# 04_IF_AMP_Block.net
KiCad netlist of a schematic drawn in Altium Designer
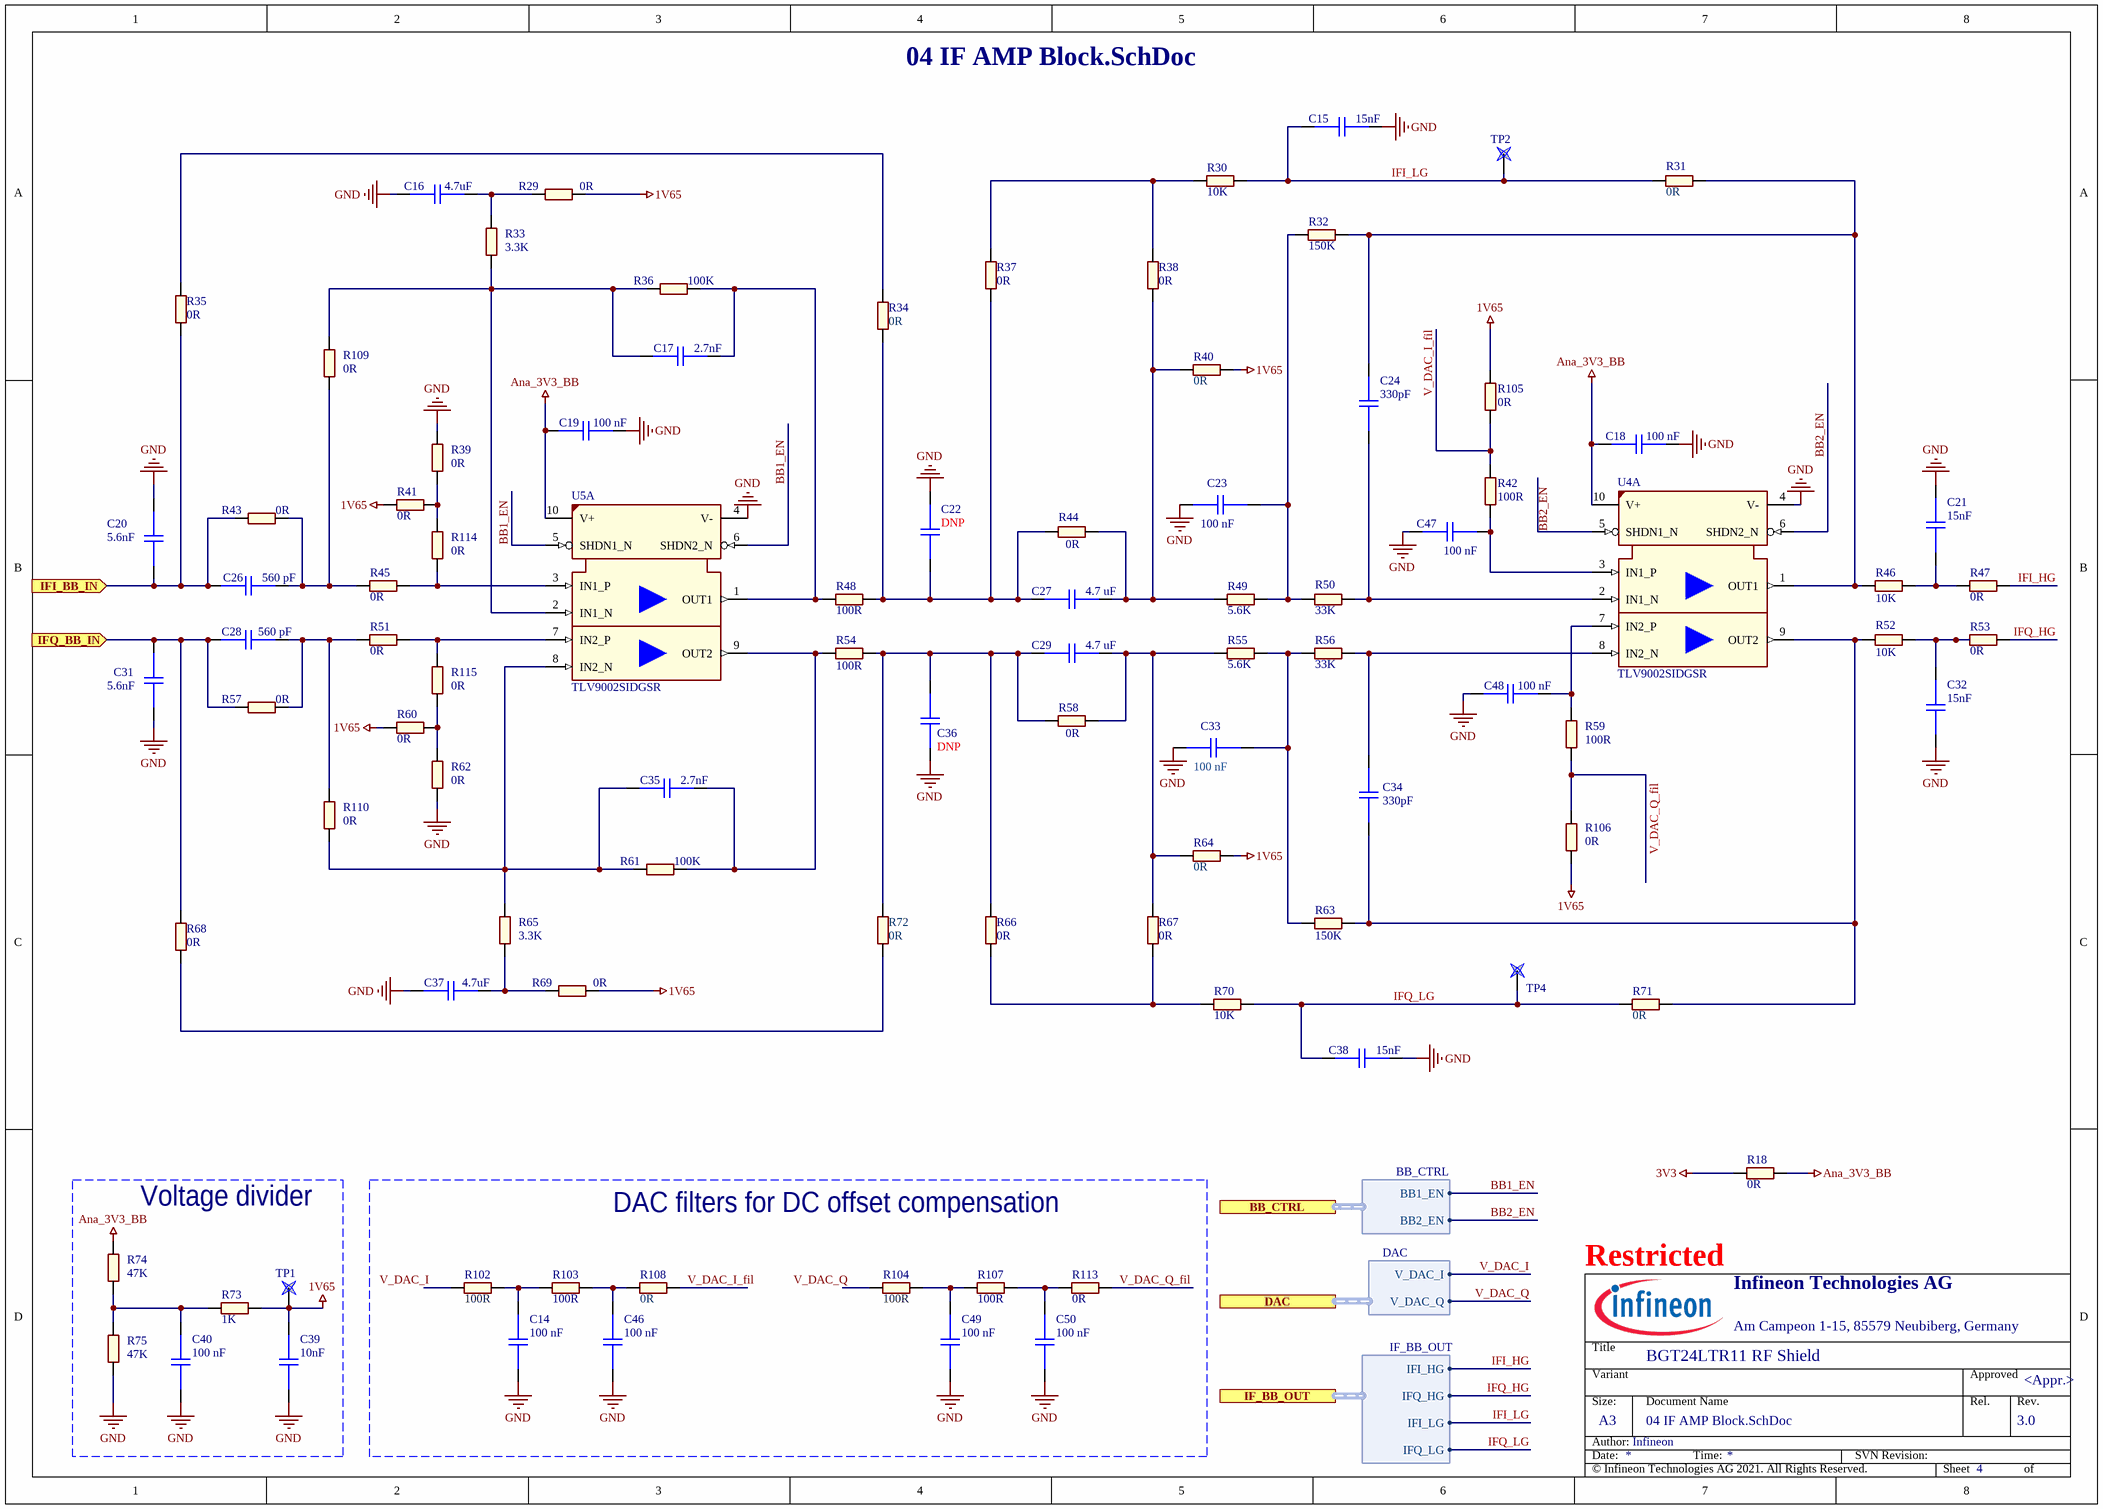
[diagram p0: 04 IF AMP Block.SchDoc]

(export (version "E")
  (design (tool "Eeschema 10.0.6"))
  (components
    (comp (ref "C14")
      (value "100 nF")
      (footprint "CAPC1005X55N-0_2")
      (description "General Purpose Surface Mount Ceramic Capacitor")
      (fields (field (name "PARTNUMBER") "CAP01010597") (field (name "VOLTAGE") "16Vdc"))
      (libsource (lib "DB_External_Capacitor") (part "c_std_a"))
    )
    (comp (ref "C15")
      (value "15nF")
      (footprint "CAPC1005X55N-0_2")
      (description "General Purpose Surface Mount Ceramic Capacitor")
      (fields (field (name "PARTNUMBER") "CAP01010597") (field (name "VOLTAGE") "25Vdc"))
      (libsource (lib "DB_External_Capacitor") (part "c_std_a"))
    )
    (comp (ref "C16")
      (value "4.7uF")
      (footprint "CAPC1005X55N-0_2")
      (description "General Purpose Surface Mount Ceramic Capacitor")
      (fields (field (name "PARTNUMBER") "CAP01010597") (field (name "VOLTAGE") "50Vdc"))
      (libsource (lib "DB_External_Capacitor") (part "c_std_a"))
    )
    (comp (ref "C17")
      (value "2.7nF")
      (footprint "CAPC1005X55N-0_2")
      (description "General Purpose Surface Mount Ceramic Capacitor")
      (fields (field (name "PARTNUMBER") "CAP01010597") (field (name "VOLTAGE") "50Vdc"))
      (libsource (lib "DB_External_Capacitor") (part "c_std_a"))
    )
    (comp (ref "C18")
      (value "100 nF")
      (footprint "CAPC1005X55N-0_2")
      (description "General Purpose Surface Mount Ceramic Capacitor")
      (fields (field (name "PARTNUMBER") "CAP01010597") (field (name "VOLTAGE") "16Vdc"))
      (libsource (lib "DB_External_Capacitor") (part "c_std_a"))
    )
    (comp (ref "C19")
      (value "100 nF")
      (footprint "CAPC1005X55N-0_2")
      (description "General Purpose Surface Mount Ceramic Capacitor")
      (fields (field (name "PARTNUMBER") "CAP01010597") (field (name "VOLTAGE") "16Vdc"))
      (libsource (lib "DB_External_Capacitor") (part "c_std_a"))
    )
    (comp (ref "C20")
      (value "5.6nF")
      (footprint "CAPC1005X55N-0_2")
      (description "General Purpose Surface Mount Ceramic Capacitor")
      (fields (field (name "PARTNUMBER") "CAP01010597") (field (name "VOLTAGE") "50Vdc"))
      (libsource (lib "DB_External_Capacitor") (part "c_std_a"))
    )
    (comp (ref "C21")
      (value "15nF")
      (footprint "CAPC1005X55N-0_2")
      (description "General Purpose Surface Mount Ceramic Capacitor")
      (fields (field (name "PARTNUMBER") "CAP01010597") (field (name "VOLTAGE") "25Vdc"))
      (libsource (lib "DB_External_Capacitor") (part "c_std_a"))
    )
    (comp (ref "C22")
      (value "DNP")
      (footprint "CAPC1005X55N-0_2")
      (description "General Purpose Surface Mount Ceramic Capacitor")
      (fields (field (name "PARTNUMBER") "CAP01010597") (field (name "VOLTAGE") "50Vdc"))
      (libsource (lib "DB_External_Capacitor") (part "c_std_a"))
    )
    (comp (ref "C23")
      (value "100 nF")
      (footprint "CAPC1005X55N-0_2")
      (description "General Purpose Surface Mount Ceramic Capacitor")
      (fields (field (name "PARTNUMBER") "CAP01010597") (field (name "VOLTAGE") "16Vdc"))
      (libsource (lib "DB_External_Capacitor") (part "c_std_a"))
    )
    (comp (ref "C24")
      (value "330pF")
      (footprint "CAPC1005X55N-0_2")
      (description "General Purpose Surface Mount Ceramic Capacitor")
      (fields (field (name "PARTNUMBER") "CAP01010597") (field (name "VOLTAGE") "50Vdc"))
      (libsource (lib "DB_External_Capacitor") (part "c_std_a"))
    )
    (comp (ref "C26")
      (value "560 pF")
      (footprint "CAPC1005X55N-0_2")
      (description "General Purpose Surface Mount Ceramic Capacitor")
      (fields (field (name "PARTNUMBER") "CAP01010597") (field (name "VOLTAGE") "50Vdc"))
      (libsource (lib "DB_External_Capacitor") (part "c_std_a"))
    )
    (comp (ref "C27")
      (value "4.7 uF")
      (footprint "CAPC1005X55N-0_2")
      (description "General Purpose Surface Mount Ceramic Capacitor")
      (fields (field (name "PARTNUMBER") "CAP01010597") (field (name "VOLTAGE") "50Vdc"))
      (libsource (lib "DB_External_Capacitor") (part "c_std_a"))
    )
    (comp (ref "C28")
      (value "560 pF")
      (footprint "CAPC1005X55N-0_2")
      (description "General Purpose Surface Mount Ceramic Capacitor")
      (fields (field (name "PARTNUMBER") "CAP01010597") (field (name "VOLTAGE") "50Vdc"))
      (libsource (lib "DB_External_Capacitor") (part "c_std_a"))
    )
    (comp (ref "C29")
      (value "4.7 uF")
      (footprint "CAPC1005X55N-0_2")
      (description "General Purpose Surface Mount Ceramic Capacitor")
      (fields (field (name "PARTNUMBER") "CAP01010597") (field (name "VOLTAGE") "50Vdc"))
      (libsource (lib "DB_External_Capacitor") (part "c_std_a"))
    )
    (comp (ref "C31")
      (value "5.6nF")
      (footprint "CAPC1005X55N-0_2")
      (description "General Purpose Surface Mount Ceramic Capacitor")
      (fields (field (name "PARTNUMBER") "CAP01010597") (field (name "VOLTAGE") "50Vdc"))
      (libsource (lib "DB_External_Capacitor") (part "c_std_a"))
    )
    (comp (ref "C32")
      (value "15nF")
      (footprint "CAPC1005X55N-0_2")
      (description "General Purpose Surface Mount Ceramic Capacitor")
      (fields (field (name "PARTNUMBER") "CAP01010597") (field (name "VOLTAGE") "25Vdc"))
      (libsource (lib "DB_External_Capacitor") (part "c_std_a"))
    )
    (comp (ref "C33")
      (value "100 nF")
      (footprint "CAPC1005X55N-0_2")
      (description "General Purpose Surface Mount Ceramic Capacitor")
      (fields (field (name "PARTNUMBER") "CAP01010597") (field (name "VOLTAGE") "16Vdc"))
      (libsource (lib "DB_External_Capacitor") (part "c_std_a"))
    )
    (comp (ref "C34")
      (value "330pF")
      (footprint "CAPC1005X55N-0_2")
      (description "General Purpose Surface Mount Ceramic Capacitor")
      (fields (field (name "PARTNUMBER") "CAP01010597") (field (name "VOLTAGE") "50Vdc"))
      (libsource (lib "DB_External_Capacitor") (part "c_std_a"))
    )
    (comp (ref "C35")
      (value "2.7nF")
      (footprint "CAPC1005X55N-0_2")
      (description "General Purpose Surface Mount Ceramic Capacitor")
      (fields (field (name "PARTNUMBER") "CAP01010597") (field (name "VOLTAGE") "50Vdc"))
      (libsource (lib "DB_External_Capacitor") (part "c_std_a"))
    )
    (comp (ref "C36")
      (value "DNP")
      (footprint "CAPC1005X55N-0_2")
      (description "General Purpose Surface Mount Ceramic Capacitor")
      (fields (field (name "PARTNUMBER") "CAP01010597") (field (name "VOLTAGE") "50Vdc"))
      (libsource (lib "DB_External_Capacitor") (part "c_std_a"))
    )
    (comp (ref "C37")
      (value "4.7uF")
      (footprint "CAPC1005X55N-0_2")
      (description "General Purpose Surface Mount Ceramic Capacitor")
      (fields (field (name "PARTNUMBER") "CAP01010597") (field (name "VOLTAGE") "50Vdc"))
      (libsource (lib "DB_External_Capacitor") (part "c_std_a"))
    )
    (comp (ref "C38")
      (value "15nF")
      (footprint "CAPC1005X55N-0_2")
      (description "General Purpose Surface Mount Ceramic Capacitor")
      (fields (field (name "PARTNUMBER") "CAP01010597") (field (name "VOLTAGE") "25Vdc"))
      (libsource (lib "DB_External_Capacitor") (part "c_std_a"))
    )
    (comp (ref "C39")
      (value "10nF")
      (footprint "CAPC1005X55N-0_2")
      (description "General Purpose Surface Mount Ceramic Capacitor")
      (fields (field (name "PARTNUMBER") "CAP01010597") (field (name "VOLTAGE") "16Vdc"))
      (libsource (lib "DB_External_Capacitor") (part "c_std_a"))
    )
    (comp (ref "C40")
      (value "100 nF")
      (footprint "CAPC1005X55N-0_2")
      (description "General Purpose Surface Mount Ceramic Capacitor")
      (fields (field (name "PARTNUMBER") "CAP01010597") (field (name "VOLTAGE") "16Vdc"))
      (libsource (lib "DB_External_Capacitor") (part "c_std_a"))
    )
    (comp (ref "C46")
      (value "100 nF")
      (footprint "CAPC1005X55N-0_2")
      (description "General Purpose Surface Mount Ceramic Capacitor")
      (fields (field (name "PARTNUMBER") "CAP01010597") (field (name "VOLTAGE") "16Vdc"))
      (libsource (lib "DB_External_Capacitor") (part "c_std_a"))
    )
    (comp (ref "C47")
      (value "100 nF")
      (footprint "CAPC1005X55N-0_2")
      (description "General Purpose Surface Mount Ceramic Capacitor")
      (fields (field (name "PARTNUMBER") "CAP01010597") (field (name "VOLTAGE") "16Vdc"))
      (libsource (lib "DB_External_Capacitor") (part "c_std_a"))
    )
    (comp (ref "C48")
      (value "100 nF")
      (footprint "CAPC1005X55N-0_2")
      (description "General Purpose Surface Mount Ceramic Capacitor")
      (fields (field (name "PARTNUMBER") "CAP01010597") (field (name "VOLTAGE") "16Vdc"))
      (libsource (lib "DB_External_Capacitor") (part "c_std_a"))
    )
    (comp (ref "C49")
      (value "100 nF")
      (footprint "CAPC1005X55N-0_2")
      (description "General Purpose Surface Mount Ceramic Capacitor")
      (fields (field (name "PARTNUMBER") "CAP01010597") (field (name "VOLTAGE") "16Vdc"))
      (libsource (lib "DB_External_Capacitor") (part "c_std_a"))
    )
    (comp (ref "C50")
      (value "100 nF")
      (footprint "CAPC1005X55N-0_2")
      (description "General Purpose Surface Mount Ceramic Capacitor")
      (fields (field (name "PARTNUMBER") "CAP01010597") (field (name "VOLTAGE") "16Vdc"))
      (libsource (lib "DB_External_Capacitor") (part "c_std_a"))
    )
    (comp (ref "R18")
      (value "0R")
      (footprint "RESC1005X40N_2")
      (description "0R/50V/20mOhm")
      (fields (field (name "PARTNUMBER") "RES01800000") (field (name "POWER") "1.5A"))
      (libsource (lib "DB_External_Resistor") (part "r_std_a"))
    )
    (comp (ref "R29")
      (value "0R")
      (footprint "RESC1005X40N_2")
      (description "0R/50V/20mOhm")
      (fields (field (name "PARTNUMBER") "RES01800000") (field (name "POWER") "1.5A"))
      (libsource (lib "") (part "r_std_a_3"))
    )
    (comp (ref "R30")
      (value "10K")
      (footprint "RESC1005X40N_2")
      (description "10K/50V/20mOhm")
      (fields (field (name "PARTNUMBER") "RES01800000") (field (name "POWER") "1.5A"))
      (libsource (lib "") (part "r_std_a_2"))
    )
    (comp (ref "R31")
      (value "0R")
      (footprint "RESC1005X40N_2")
      (description "0R/50V/20mOhm")
      (fields (field (name "PARTNUMBER") "RES01800000") (field (name "POWER") "1.5A"))
      (libsource (lib "") (part "r_std_a_3"))
    )
    (comp (ref "R32")
      (value "150K")
      (footprint "RESC1005X40N_2")
      (description "150K/50V/20mOhm")
      (fields (field (name "PARTNUMBER") "RES01800000") (field (name "POWER") "1.5A"))
      (libsource (lib "DB_External_Resistor") (part "r_std_a"))
    )
    (comp (ref "R33")
      (value "3.3K")
      (footprint "RESC1005X40N_2")
      (description "3.3K/50V/20mOhm")
      (fields (field (name "PARTNUMBER") "RES01800000") (field (name "POWER") "1.5A"))
      (libsource (lib "") (part "r_std_a_2"))
    )
    (comp (ref "R34")
      (value "0R")
      (footprint "RESC1005X40N_2")
      (description "0R/50V/20mOhm")
      (fields (field (name "PARTNUMBER") "RES01800000") (field (name "POWER") "1.5A"))
      (libsource (lib "DB_External_Resistor") (part "r_std_a"))
    )
    (comp (ref "R35")
      (value "0R")
      (footprint "RESC1005X40N_2")
      (description "0R/50V/20mOhm")
      (fields (field (name "PARTNUMBER") "RES01800000") (field (name "POWER") "1.5A"))
      (libsource (lib "DB_External_Resistor") (part "r_std_a"))
    )
    (comp (ref "R36")
      (value "100K")
      (footprint "RESC1005X40N_2")
      (description "100K/50V/0402")
      (fields (field (name "PARTNUMBER") "RES01800000") (field (name "POWER") "1.5A"))
      (libsource (lib "") (part "r_std_a_3"))
    )
    (comp (ref "R37")
      (value "0R")
      (footprint "RESC1005X40N_2")
      (description "0R/50V/20mOhm")
      (fields (field (name "PARTNUMBER") "RES01800000") (field (name "POWER") "1.5A"))
      (libsource (lib "") (part "r_std_a_1"))
    )
    (comp (ref "R38")
      (value "0R")
      (footprint "RESC1005X40N_2")
      (description "0R/50V/20mOhm")
      (fields (field (name "PARTNUMBER") "RES01800000") (field (name "POWER") "1.5A"))
      (libsource (lib "") (part "r_std_a_1"))
    )
    (comp (ref "R39")
      (value "0R")
      (footprint "RESC1005X40N_2")
      (description "0R/50V/20mOhm")
      (fields (field (name "PARTNUMBER") "RES01800000") (field (name "POWER") "1.5A"))
      (libsource (lib "") (part "r_std_a_1"))
    )
    (comp (ref "R40")
      (value "0R")
      (footprint "RESC1005X40N_2")
      (description "0R/50V/20mOhm")
      (fields (field (name "PARTNUMBER") "RES01800000") (field (name "POWER") "1.5A"))
      (libsource (lib "") (part "r_std_a_3"))
    )
    (comp (ref "R41")
      (value "0R")
      (footprint "RESC1005X40N_2")
      (description "0R/50V/20mOhm")
      (fields (field (name "PARTNUMBER") "RES01800000") (field (name "POWER") "1.5A"))
      (libsource (lib "") (part "r_std_a_2"))
    )
    (comp (ref "R42")
      (value "100R")
      (footprint "RESC1005X40N_2")
      (description "100R/50V/0402")
      (fields (field (name "PARTNUMBER") "RES01800000") (field (name "POWER") "1.5A"))
      (libsource (lib "") (part "r_std_a_2"))
    )
    (comp (ref "R43")
      (value "0R")
      (footprint "RESC1005X40N_2")
      (description "0R/50V/20mOhm")
      (fields (field (name "PARTNUMBER") "RES01800000") (field (name "POWER") "1.5A"))
      (libsource (lib "") (part "r_std_a_3"))
    )
    (comp (ref "R44")
      (value "0R")
      (footprint "RESC1005X40N_2")
      (description "0R/50V/20mOhm")
      (fields (field (name "PARTNUMBER") "RES01800000") (field (name "POWER") "1.5A"))
      (libsource (lib "") (part "r_std_a_3"))
    )
    (comp (ref "R45")
      (value "0R")
      (footprint "RESC1005X40N_2")
      (description "0R/50V/20mOhm")
      (fields (field (name "PARTNUMBER") "RES01800000") (field (name "POWER") "1.5A"))
      (libsource (lib "") (part "r_std_a_3"))
    )
    (comp (ref "R46")
      (value "10K")
      (footprint "RESC1005X40N_2")
      (description "10K/50V/20mOhm")
      (fields (field (name "PARTNUMBER") "RES01800000") (field (name "POWER") "1.5A"))
      (libsource (lib "") (part "r_std_a_3"))
    )
    (comp (ref "R47")
      (value "0R")
      (footprint "RESC1005X40N_2")
      (description "0R/50V/20mOhm")
      (fields (field (name "PARTNUMBER") "RES01800000") (field (name "POWER") "1.5A"))
      (libsource (lib "") (part "r_std_a_3"))
    )
    (comp (ref "R48")
      (value "100R")
      (footprint "RESC1005X40N_2")
      (description "100R/50V/0402")
      (fields (field (name "PARTNUMBER") "RES01800000") (field (name "POWER") "1.5A"))
      (libsource (lib "") (part "r_std_a_3"))
    )
    (comp (ref "R49")
      (value "5.6K")
      (footprint "RESC1005X40N_2")
      (description "5.6K/50V/20mOhm")
      (fields (field (name "PARTNUMBER") "RES01800000") (field (name "POWER") "1.5A"))
      (libsource (lib "") (part "r_std_a_3"))
    )
    (comp (ref "R50")
      (value "33K")
      (footprint "RESC1005X40N_2")
      (description "5.6K/50V/20mOhm")
      (fields (field (name "PARTNUMBER") "RES01800000") (field (name "POWER") "1.5A"))
      (libsource (lib "") (part "r_std_a_3"))
    )
    (comp (ref "R51")
      (value "0R")
      (footprint "RESC1005X40N_2")
      (description "0R/50V/20mOhm")
      (fields (field (name "PARTNUMBER") "RES01800000") (field (name "POWER") "1.5A"))
      (libsource (lib "DB_External_Resistor") (part "r_std_a"))
    )
    (comp (ref "R52")
      (value "10K")
      (footprint "RESC1005X40N_2")
      (description "10K/50V/20mOhm")
      (fields (field (name "PARTNUMBER") "RES01800000") (field (name "POWER") "1.5A"))
      (libsource (lib "") (part "r_std_a_3"))
    )
    (comp (ref "R53")
      (value "0R")
      (footprint "RESC1005X40N_2")
      (description "0R/50V/20mOhm")
      (fields (field (name "PARTNUMBER") "RES01800000") (field (name "POWER") "1.5A"))
      (libsource (lib "") (part "r_std_a_3"))
    )
    (comp (ref "R54")
      (value "100R")
      (footprint "RESC1005X40N_2")
      (description "100R/50V/0402")
      (fields (field (name "PARTNUMBER") "RES01800000") (field (name "POWER") "1.5A"))
      (libsource (lib "DB_External_Resistor") (part "r_std_a"))
    )
    (comp (ref "R55")
      (value "5.6K")
      (footprint "RESC1005X40N_2")
      (description "5.6K/50V/20mOhm")
      (fields (field (name "PARTNUMBER") "RES01800000") (field (name "POWER") "1.5A"))
      (libsource (lib "DB_External_Resistor") (part "r_std_a"))
    )
    (comp (ref "R56")
      (value "33K")
      (footprint "RESC1005X40N_2")
      (description "5.6K/50V/20mOhm")
      (fields (field (name "PARTNUMBER") "RES01800000") (field (name "POWER") "1.5A"))
      (libsource (lib "DB_External_Resistor") (part "r_std_a"))
    )
    (comp (ref "R57")
      (value "0R")
      (footprint "RESC1005X40N_2")
      (description "0R/50V/20mOhm")
      (fields (field (name "PARTNUMBER") "RES01800000") (field (name "POWER") "1.5A"))
      (libsource (lib "DB_External_Resistor") (part "r_std_a"))
    )
    (comp (ref "R58")
      (value "0R")
      (footprint "RESC1005X40N_2")
      (description "0R/50V/20mOhm")
      (fields (field (name "PARTNUMBER") "RES01800000") (field (name "POWER") "1.5A"))
      (libsource (lib "DB_External_Resistor") (part "r_std_a"))
    )
    (comp (ref "R59")
      (value "100R")
      (footprint "RESC1005X40N_2")
      (description "100R/50V/0402")
      (fields (field (name "PARTNUMBER") "RES01800000") (field (name "POWER") "1.5A"))
      (libsource (lib "DB_External_Resistor") (part "r_std_a"))
    )
    (comp (ref "R60")
      (value "0R")
      (footprint "RESC1005X40N_2")
      (description "0R/50V/20mOhm")
      (fields (field (name "PARTNUMBER") "RES01800000") (field (name "POWER") "1.5A"))
      (libsource (lib "") (part "r_std_a_2"))
    )
    (comp (ref "R61")
      (value "100K")
      (footprint "RESC1005X40N_2")
      (description "100K/50V/0402")
      (fields (field (name "PARTNUMBER") "RES01800000") (field (name "POWER") "1.5A"))
      (libsource (lib "DB_External_Resistor") (part "r_std_a"))
    )
    (comp (ref "R62")
      (value "0R")
      (footprint "RESC1005X40N_2")
      (description "0R/50V/20mOhm")
      (fields (field (name "PARTNUMBER") "RES01800000") (field (name "POWER") "1.5A"))
      (libsource (lib "DB_External_Resistor") (part "r_std_a"))
    )
    (comp (ref "R63")
      (value "150K")
      (footprint "RESC1005X40N_2")
      (description "150K/50V/20mOhm")
      (fields (field (name "PARTNUMBER") "RES01800000") (field (name "POWER") "1.5A"))
      (libsource (lib "DB_External_Resistor") (part "r_std_a"))
    )
    (comp (ref "R64")
      (value "0R")
      (footprint "RESC1005X40N_2")
      (description "0R/50V/20mOhm")
      (fields (field (name "PARTNUMBER") "RES01800000") (field (name "POWER") "1.5A"))
      (libsource (lib "") (part "r_std_a_3"))
    )
    (comp (ref "R65")
      (value "3.3K")
      (footprint "RESC1005X40N_2")
      (description "3.3K/50V/20mOhm")
      (fields (field (name "PARTNUMBER") "RES01800000") (field (name "POWER") "1.5A"))
      (libsource (lib "") (part "r_std_a_3"))
    )
    (comp (ref "R66")
      (value "0R")
      (footprint "RESC1005X40N_2")
      (description "0R/50V/20mOhm")
      (fields (field (name "PARTNUMBER") "RES01800000") (field (name "POWER") "1.5A"))
      (libsource (lib "") (part "r_std_a_1"))
    )
    (comp (ref "R67")
      (value "0R")
      (footprint "RESC1005X40N_2")
      (description "0R/50V/20mOhm")
      (fields (field (name "PARTNUMBER") "RES01800000") (field (name "POWER") "1.5A"))
      (libsource (lib "") (part "r_std_a_1"))
    )
    (comp (ref "R68")
      (value "0R")
      (footprint "RESC1005X40N_2")
      (description "0R/50V/20mOhm")
      (fields (field (name "PARTNUMBER") "RES01800000") (field (name "POWER") "1.5A"))
      (libsource (lib "DB_External_Resistor") (part "r_std_a"))
    )
    (comp (ref "R69")
      (value "0R")
      (footprint "RESC1005X40N_2")
      (description "0R/50V/20mOhm")
      (fields (field (name "PARTNUMBER") "RES01800000") (field (name "POWER") "1.5A"))
      (libsource (lib "DB_External_Resistor") (part "r_std_a"))
    )
    (comp (ref "R70")
      (value "10K")
      (footprint "RESC1005X40N_2")
      (description "10K/50V/20mOhm")
      (fields (field (name "PARTNUMBER") "RES01800000") (field (name "POWER") "1.5A"))
      (libsource (lib "") (part "r_std_a_1"))
    )
    (comp (ref "R71")
      (value "0R")
      (footprint "RESC1005X40N_2")
      (description "0R/50V/20mOhm")
      (fields (field (name "PARTNUMBER") "RES01800000") (field (name "POWER") "1.5A"))
      (libsource (lib "") (part "r_std_a_3"))
    )
    (comp (ref "R72")
      (value "0R")
      (footprint "RESC1005X40N_2")
      (description "0R/50V/20mOhm")
      (fields (field (name "PARTNUMBER") "RES01800000") (field (name "POWER") "1.5A"))
      (libsource (lib "DB_External_Resistor") (part "r_std_a"))
    )
    (comp (ref "R73")
      (value "1K")
      (footprint "RESC1005X40N_2")
      (description "1K/50V/20mOhm")
      (fields (field (name "PARTNUMBER") "RES01800000") (field (name "POWER") "1.5A"))
      (libsource (lib "") (part "r_std_a_3"))
    )
    (comp (ref "R74")
      (value "47K")
      (footprint "RESC1005X40N_2")
      (description "47K/50V/20mOhm")
      (fields (field (name "PARTNUMBER") "RES01800000") (field (name "POWER") "1.5A"))
      (libsource (lib "") (part "r_std_a_2"))
    )
    (comp (ref "R75")
      (value "47K")
      (footprint "RESC1005X40N_2")
      (description "47K/50V/20mOhm")
      (fields (field (name "PARTNUMBER") "RES01800000") (field (name "POWER") "1.5A"))
      (libsource (lib "DB_External_Resistor") (part "r_std_a"))
    )
    (comp (ref "R102")
      (value "100R")
      (footprint "RESC1005X40N_2")
      (description "100R/50V/0402")
      (fields (field (name "PARTNUMBER") "RES01800000") (field (name "POWER") "1.5A"))
      (libsource (lib "") (part "r_std_a_3"))
    )
    (comp (ref "R103")
      (value "100R")
      (footprint "RESC1005X40N_2")
      (description "100R/50V/0402")
      (fields (field (name "PARTNUMBER") "RES01800000") (field (name "POWER") "1.5A"))
      (libsource (lib "") (part "r_std_a_3"))
    )
    (comp (ref "R104")
      (value "100R")
      (footprint "RESC1005X40N_2")
      (description "100R/50V/0402")
      (fields (field (name "PARTNUMBER") "RES01800000") (field (name "POWER") "1.5A"))
      (libsource (lib "") (part "r_std_a_3"))
    )
    (comp (ref "R105")
      (value "0R")
      (footprint "RESC1005X40N_2")
      (description "0R/50V/20mOhm")
      (fields (field (name "PARTNUMBER") "RES01800000") (field (name "POWER") "1.5A"))
      (libsource (lib "") (part "r_std_a_2"))
    )
    (comp (ref "R106")
      (value "0R")
      (footprint "RESC1005X40N_2")
      (description "0R/50V/20mOhm")
      (fields (field (name "PARTNUMBER") "RES01800000") (field (name "POWER") "1.5A"))
      (libsource (lib "") (part "r_std_a_2"))
    )
    (comp (ref "R107")
      (value "100R")
      (footprint "RESC1005X40N_2")
      (description "100R/50V/0402")
      (fields (field (name "PARTNUMBER") "RES01800000") (field (name "POWER") "1.5A"))
      (libsource (lib "") (part "r_std_a_3"))
    )
    (comp (ref "R108")
      (value "0R")
      (footprint "RESC1005X40N_2")
      (description "0R/50V/20mOhm")
      (fields (field (name "PARTNUMBER") "RES01800000") (field (name "POWER") "1.5A"))
      (libsource (lib "") (part "r_std_a_3"))
    )
    (comp (ref "R109")
      (value "0R")
      (footprint "RESC1005X40N_2")
      (description "0R/50V/20mOhm")
      (fields (field (name "PARTNUMBER") "RES01800000") (field (name "POWER") "1.5A"))
      (libsource (lib "") (part "r_std_a_1"))
    )
    (comp (ref "R110")
      (value "0R")
      (footprint "RESC1005X40N_2")
      (description "0R/50V/20mOhm")
      (fields (field (name "PARTNUMBER") "RES01800000") (field (name "POWER") "1.5A"))
      (libsource (lib "") (part "r_std_a_1"))
    )
    (comp (ref "R113")
      (value "0R")
      (footprint "RESC1005X40N_2")
      (description "0R/50V/20mOhm")
      (fields (field (name "PARTNUMBER") "RES01800000") (field (name "POWER") "1.5A"))
      (libsource (lib "") (part "r_std_a_3"))
    )
    (comp (ref "R114")
      (value "0R")
      (footprint "RESC1005X40N_2")
      (description "0R/50V/20mOhm")
      (fields (field (name "PARTNUMBER") "RES01800000") (field (name "POWER") "1.5A"))
      (libsource (lib "") (part "r_std_a_3"))
    )
    (comp (ref "R115")
      (value "0R")
      (footprint "RESC1005X40N_2")
      (description "0R/50V/20mOhm")
      (fields (field (name "PARTNUMBER") "RES01800000") (field (name "POWER") "1.5A"))
      (libsource (lib "") (part "r_std_a_3"))
    )
    (comp (ref "TP1")
      (value "Testpoint")
      (footprint "TP1.5MM")
      (libsource (lib "altium-import") (part "root_0_P_PRUEFPAD_"))
    )
    (comp (ref "TP2")
      (value "Testpoint")
      (footprint "TP1.5MM")
      (libsource (lib "altium-import") (part "root_0_P_PRUEFPAD_"))
    )
    (comp (ref "TP4")
      (value "Testpoint")
      (footprint "TP1.5MM")
      (libsource (lib "altium-import") (part "root_0_P_PRUEFPAD_"))
    )
    (comp (ref "U4")
      (value "TLV9002SIDGSR")
      (footprint "SOP50P490X110-10N-1-V")
      (description "Op Amp Dual Low Power Amplifier R-R I/O Â±2.75V/5.5V")
      (fields (field (name "MANUFACTURER") "Texas Instruments"))
      (libsource (lib "PCBLibraryData") (part "TLV9002SIDGSR"))
    )
    (comp (ref "U5")
      (value "TLV9002SIDGSR")
      (footprint "SOP50P490X110-10N-1-V")
      (description "Op Amp Dual Low Power Amplifier R-R I/O Â±2.75V/5.5V")
      (fields (field (name "MANUFACTURER") "Texas Instruments"))
      (libsource (lib "PCBLibraryData") (part "TLV9002SIDGSR"))
    )
  )
  (nets
    (net (code "4") (name "/BB1_EN") (class "Default")
      (node (ref "U5") (pin "5") (pinfunction "SHDN1_N_5") (pintype "input"))
      (node (ref "U5") (pin "6") (pinfunction "SHDN2_N_6") (pintype "input"))
    )
    (net (code "5") (name "/BB2_EN") (class "Default")
      (node (ref "U4") (pin "5") (pinfunction "SHDN1_N_5") (pintype "input"))
      (node (ref "U4") (pin "6") (pinfunction "SHDN2_N_6") (pintype "input"))
    )
    (net (code "6") (name "/IFI_BB_IN") (class "Default")
      (node (ref "C20") (pin "2") (pinfunction "2_2") (pintype "passive"))
      (node (ref "C26") (pin "2") (pinfunction "2_2") (pintype "passive"))
      (node (ref "R35") (pin "2") (pinfunction "2_2") (pintype "passive"))
      (node (ref "R43") (pin "2") (pinfunction "2_2") (pintype "passive"))
    )
    (net (code "7") (name "/IFI_HG") (class "Default")
      (node (ref "R47") (pin "1") (pinfunction "1_1") (pintype "passive"))
    )
    (net (code "8") (name "/IFI_LG") (class "Default")
      (node (ref "C15") (pin "1") (pinfunction "1_1") (pintype "passive"))
      (node (ref "R30") (pin "2") (pinfunction "2_2") (pintype "passive"))
      (node (ref "R31") (pin "2") (pinfunction "2_2") (pintype "passive"))
      (node (ref "TP2") (pin "1") (pinfunction "1_1") (pintype "passive"))
    )
    (net (code "9") (name "/IFQ_BB_IN") (class "Default")
      (node (ref "C28") (pin "2") (pinfunction "2_2") (pintype "passive"))
      (node (ref "C31") (pin "2") (pinfunction "2_2") (pintype "passive"))
      (node (ref "R57") (pin "2") (pinfunction "2_2") (pintype "passive"))
      (node (ref "R68") (pin "1") (pinfunction "1_1") (pintype "passive"))
    )
    (net (code "10") (name "/IFQ_HG") (class "Default")
      (node (ref "R53") (pin "1") (pinfunction "1_1") (pintype "passive"))
    )
    (net (code "11") (name "/IFQ_LG") (class "Default")
      (node (ref "C38") (pin "2") (pinfunction "2_2") (pintype "passive"))
      (node (ref "R70") (pin "2") (pinfunction "2_2") (pintype "passive"))
      (node (ref "R71") (pin "2") (pinfunction "2_2") (pintype "passive"))
      (node (ref "TP4") (pin "1") (pinfunction "1_1") (pintype "passive"))
    )
    (net (code "12") (name "/V_DAC_I") (class "Default")
      (node (ref "R102") (pin "2") (pinfunction "2_2") (pintype "passive"))
    )
    (net (code "13") (name "/V_DAC_I_fil") (class "Default")
      (node (ref "R105") (pin "1") (pinfunction "1_1") (pintype "passive"))
      (node (ref "R108") (pin "1") (pinfunction "1_1") (pintype "passive"))
      (node (ref "R42") (pin "2") (pinfunction "2_2") (pintype "passive"))
    )
    (net (code "14") (name "/V_DAC_Q") (class "Default")
      (node (ref "R104") (pin "2") (pinfunction "2_2") (pintype "passive"))
    )
    (net (code "15") (name "/V_DAC_Q_fil") (class "Default")
      (node (ref "R106") (pin "2") (pinfunction "2_2") (pintype "passive"))
      (node (ref "R113") (pin "1") (pinfunction "1_1") (pintype "passive"))
      (node (ref "R59") (pin "2") (pinfunction "2_2") (pintype "passive"))
    )
    (net (code "19") (name "1V65") (class "Default")
      (node (ref "C39") (pin "1") (pinfunction "1_1") (pintype "passive"))
      (node (ref "R105") (pin "2") (pinfunction "2_2") (pintype "passive"))
      (node (ref "R106") (pin "1") (pinfunction "1_1") (pintype "passive"))
      (node (ref "R29") (pin "1") (pinfunction "1_1") (pintype "passive"))
      (node (ref "R40") (pin "1") (pinfunction "1_1") (pintype "passive"))
      (node (ref "R41") (pin "1") (pinfunction "1_1") (pintype "passive"))
      (node (ref "R60") (pin "1") (pinfunction "1_1") (pintype "passive"))
      (node (ref "R64") (pin "1") (pinfunction "1_1") (pintype "passive"))
      (node (ref "R69") (pin "1") (pinfunction "1_1") (pintype "passive"))
      (node (ref "R73") (pin "1") (pinfunction "1_1") (pintype "passive"))
      (node (ref "TP1") (pin "1") (pinfunction "1_1") (pintype "passive"))
    )
    (net (code "20") (name "3V3") (class "Default")
      (node (ref "R18") (pin "2") (pinfunction "2_2") (pintype "passive"))
    )
    (net (code "21") (name "Ana_3V3_BB") (class "Default")
      (node (ref "C18") (pin "2") (pinfunction "2_2") (pintype "passive"))
      (node (ref "C19") (pin "2") (pinfunction "2_2") (pintype "passive"))
      (node (ref "R18") (pin "1") (pinfunction "1_1") (pintype "passive"))
      (node (ref "R74") (pin "2") (pinfunction "2_2") (pintype "passive"))
      (node (ref "U4") (pin "10") (pinfunction "V+_10") (pintype "power_in"))
      (node (ref "U5") (pin "10") (pinfunction "V+_10") (pintype "power_in"))
    )
    (net (code "22") (name "GND") (class "Default")
      (node (ref "C14") (pin "1") (pinfunction "1_1") (pintype "passive"))
      (node (ref "C15") (pin "2") (pinfunction "2_2") (pintype "passive"))
      (node (ref "C16") (pin "1") (pinfunction "1_1") (pintype "passive"))
      (node (ref "C18") (pin "1") (pinfunction "1_1") (pintype "passive"))
      (node (ref "C19") (pin "1") (pinfunction "1_1") (pintype "passive"))
      (node (ref "C20") (pin "1") (pinfunction "1_1") (pintype "passive"))
      (node (ref "C21") (pin "1") (pinfunction "1_1") (pintype "passive"))
      (node (ref "C22") (pin "1") (pinfunction "1_1") (pintype "passive"))
      (node (ref "C23") (pin "2") (pinfunction "2_2") (pintype "passive"))
      (node (ref "C31") (pin "1") (pinfunction "1_1") (pintype "passive"))
      (node (ref "C32") (pin "2") (pinfunction "2_2") (pintype "passive"))
      (node (ref "C33") (pin "2") (pinfunction "2_2") (pintype "passive"))
      (node (ref "C36") (pin "2") (pinfunction "2_2") (pintype "passive"))
      (node (ref "C37") (pin "2") (pinfunction "2_2") (pintype "passive"))
      (node (ref "C38") (pin "1") (pinfunction "1_1") (pintype "passive"))
      (node (ref "C39") (pin "2") (pinfunction "2_2") (pintype "passive"))
      (node (ref "C40") (pin "2") (pinfunction "2_2") (pintype "passive"))
      (node (ref "C46") (pin "1") (pinfunction "1_1") (pintype "passive"))
      (node (ref "C47") (pin "2") (pinfunction "2_2") (pintype "passive"))
      (node (ref "C48") (pin "1") (pinfunction "1_1") (pintype "passive"))
      (node (ref "C49") (pin "1") (pinfunction "1_1") (pintype "passive"))
      (node (ref "C50") (pin "1") (pinfunction "1_1") (pintype "passive"))
      (node (ref "R39") (pin "2") (pinfunction "2_2") (pintype "passive"))
      (node (ref "R62") (pin "2") (pinfunction "2_2") (pintype "passive"))
      (node (ref "R75") (pin "2") (pinfunction "2_2") (pintype "passive"))
      (node (ref "U4") (pin "4") (pinfunction "V-_4") (pintype "power_in"))
      (node (ref "U5") (pin "4") (pinfunction "V-_4") (pintype "power_in"))
    )
    (net (code "23") (name "Net-(C14-Pad2)") (class "Default")
      (node (ref "C14") (pin "2") (pinfunction "2_2") (pintype "passive"))
      (node (ref "R102") (pin "1") (pinfunction "1_1") (pintype "passive"))
      (node (ref "R103") (pin "2") (pinfunction "2_2") (pintype "passive"))
    )
    (net (code "24") (name "Net-(C16-Pad2)") (class "Default")
      (node (ref "C16") (pin "2") (pinfunction "2_2") (pintype "passive"))
      (node (ref "R29") (pin "2") (pinfunction "2_2") (pintype "passive"))
      (node (ref "R33") (pin "2") (pinfunction "2_2") (pintype "passive"))
    )
    (net (code "25") (name "Net-(C21-Pad2)") (class "Default")
      (node (ref "C21") (pin "2") (pinfunction "2_2") (pintype "passive"))
      (node (ref "R46") (pin "1") (pinfunction "1_1") (pintype "passive"))
      (node (ref "R47") (pin "2") (pinfunction "2_2") (pintype "passive"))
    )
    (net (code "26") (name "Net-(C22-Pad2)") (class "Default")
      (node (ref "C22") (pin "2") (pinfunction "2_2") (pintype "passive"))
      (node (ref "C27") (pin "2") (pinfunction "2_2") (pintype "passive"))
      (node (ref "R34") (pin "2") (pinfunction "2_2") (pintype "passive"))
      (node (ref "R37") (pin "1") (pinfunction "1_1") (pintype "passive"))
      (node (ref "R44") (pin "2") (pinfunction "2_2") (pintype "passive"))
      (node (ref "R48") (pin "1") (pinfunction "1_1") (pintype "passive"))
    )
    (net (code "27") (name "Net-(C23-Pad1)") (class "Default")
      (node (ref "C23") (pin "1") (pinfunction "1_1") (pintype "passive"))
      (node (ref "R32") (pin "2") (pinfunction "2_2") (pintype "passive"))
      (node (ref "R49") (pin "1") (pinfunction "1_1") (pintype "passive"))
      (node (ref "R50") (pin "2") (pinfunction "2_2") (pintype "passive"))
    )
    (net (code "28") (name "Net-(C26-Pad1)") (class "Default")
      (node (ref "C26") (pin "1") (pinfunction "1_1") (pintype "passive"))
      (node (ref "R109") (pin "1") (pinfunction "1_1") (pintype "passive"))
      (node (ref "R43") (pin "1") (pinfunction "1_1") (pintype "passive"))
      (node (ref "R45") (pin "2") (pinfunction "2_2") (pintype "passive"))
    )
    (net (code "29") (name "Net-(C27-Pad1)") (class "Default")
      (node (ref "C27") (pin "1") (pinfunction "1_1") (pintype "passive"))
      (node (ref "R38") (pin "1") (pinfunction "1_1") (pintype "passive"))
      (node (ref "R40") (pin "2") (pinfunction "2_2") (pintype "passive"))
      (node (ref "R44") (pin "1") (pinfunction "1_1") (pintype "passive"))
      (node (ref "R49") (pin "2") (pinfunction "2_2") (pintype "passive"))
    )
    (net (code "30") (name "Net-(C28-Pad1)") (class "Default")
      (node (ref "C28") (pin "1") (pinfunction "1_1") (pintype "passive"))
      (node (ref "R110") (pin "2") (pinfunction "2_2") (pintype "passive"))
      (node (ref "R51") (pin "2") (pinfunction "2_2") (pintype "passive"))
      (node (ref "R57") (pin "1") (pinfunction "1_1") (pintype "passive"))
    )
    (net (code "31") (name "Net-(C29-Pad1)") (class "Default")
      (node (ref "C29") (pin "1") (pinfunction "1_1") (pintype "passive"))
      (node (ref "R55") (pin "2") (pinfunction "2_2") (pintype "passive"))
      (node (ref "R58") (pin "1") (pinfunction "1_1") (pintype "passive"))
      (node (ref "R64") (pin "2") (pinfunction "2_2") (pintype "passive"))
      (node (ref "R67") (pin "2") (pinfunction "2_2") (pintype "passive"))
    )
    (net (code "32") (name "Net-(C29-Pad2)") (class "Default")
      (node (ref "C29") (pin "2") (pinfunction "2_2") (pintype "passive"))
      (node (ref "C36") (pin "1") (pinfunction "1_1") (pintype "passive"))
      (node (ref "R54") (pin "1") (pinfunction "1_1") (pintype "passive"))
      (node (ref "R58") (pin "2") (pinfunction "2_2") (pintype "passive"))
      (node (ref "R66") (pin "2") (pinfunction "2_2") (pintype "passive"))
      (node (ref "R72") (pin "1") (pinfunction "1_1") (pintype "passive"))
    )
    (net (code "33") (name "Net-(C32-Pad1)") (class "Default")
      (node (ref "C32") (pin "1") (pinfunction "1_1") (pintype "passive"))
      (node (ref "R52") (pin "1") (pinfunction "1_1") (pintype "passive"))
      (node (ref "R53") (pin "2") (pinfunction "2_2") (pintype "passive"))
    )
    (net (code "34") (name "Net-(C33-Pad1)") (class "Default")
      (node (ref "C33") (pin "1") (pinfunction "1_1") (pintype "passive"))
      (node (ref "R55") (pin "1") (pinfunction "1_1") (pintype "passive"))
      (node (ref "R56") (pin "2") (pinfunction "2_2") (pintype "passive"))
      (node (ref "R63") (pin "2") (pinfunction "2_2") (pintype "passive"))
    )
    (net (code "35") (name "Net-(C37-Pad1)") (class "Default")
      (node (ref "C37") (pin "1") (pinfunction "1_1") (pintype "passive"))
      (node (ref "R65") (pin "2") (pinfunction "2_2") (pintype "passive"))
      (node (ref "R69") (pin "2") (pinfunction "2_2") (pintype "passive"))
    )
    (net (code "36") (name "Net-(C40-Pad1)") (class "Default")
      (node (ref "C40") (pin "1") (pinfunction "1_1") (pintype "passive"))
      (node (ref "R73") (pin "2") (pinfunction "2_2") (pintype "passive"))
      (node (ref "R74") (pin "1") (pinfunction "1_1") (pintype "passive"))
      (node (ref "R75") (pin "1") (pinfunction "1_1") (pintype "passive"))
    )
    (net (code "37") (name "Net-(C46-Pad2)") (class "Default")
      (node (ref "C46") (pin "2") (pinfunction "2_2") (pintype "passive"))
      (node (ref "R103") (pin "1") (pinfunction "1_1") (pintype "passive"))
      (node (ref "R108") (pin "2") (pinfunction "2_2") (pintype "passive"))
    )
    (net (code "38") (name "Net-(C49-Pad2)") (class "Default")
      (node (ref "C49") (pin "2") (pinfunction "2_2") (pintype "passive"))
      (node (ref "R104") (pin "1") (pinfunction "1_1") (pintype "passive"))
      (node (ref "R107") (pin "2") (pinfunction "2_2") (pintype "passive"))
    )
    (net (code "39") (name "Net-(C50-Pad2)") (class "Default")
      (node (ref "C50") (pin "2") (pinfunction "2_2") (pintype "passive"))
      (node (ref "R107") (pin "1") (pinfunction "1_1") (pintype "passive"))
      (node (ref "R113") (pin "2") (pinfunction "2_2") (pintype "passive"))
    )
    (net (code "40") (name "Net-(R30-Pad1)") (class "Default")
      (node (ref "R30") (pin "1") (pinfunction "1_1") (pintype "passive"))
      (node (ref "R37") (pin "2") (pinfunction "2_2") (pintype "passive"))
      (node (ref "R38") (pin "2") (pinfunction "2_2") (pintype "passive"))
    )
    (net (code "41") (name "Net-(R34-Pad1)") (class "Default")
      (node (ref "R34") (pin "1") (pinfunction "1_1") (pintype "passive"))
      (node (ref "R35") (pin "1") (pinfunction "1_1") (pintype "passive"))
    )
    (net (code "42") (name "Net-(R66-Pad1)") (class "Default")
      (node (ref "R66") (pin "1") (pinfunction "1_1") (pintype "passive"))
      (node (ref "R67") (pin "1") (pinfunction "1_1") (pintype "passive"))
      (node (ref "R70") (pin "1") (pinfunction "1_1") (pintype "passive"))
    )
    (net (code "43") (name "Net-(R68-Pad2)") (class "Default")
      (node (ref "R68") (pin "2") (pinfunction "2_2") (pintype "passive"))
      (node (ref "R72") (pin "2") (pinfunction "2_2") (pintype "passive"))
    )
    (net (code "44") (name "Net-(R114-Pad1)") (class "Default")
      (node (ref "R114") (pin "1") (pinfunction "1_1") (pintype "passive"))
      (node (ref "R39") (pin "1") (pinfunction "1_1") (pintype "passive"))
      (node (ref "R41") (pin "2") (pinfunction "2_2") (pintype "passive"))
    )
    (net (code "45") (name "Net-(R115-Pad2)") (class "Default")
      (node (ref "R115") (pin "2") (pinfunction "2_2") (pintype "passive"))
      (node (ref "R60") (pin "2") (pinfunction "2_2") (pintype "passive"))
      (node (ref "R62") (pin "1") (pinfunction "1_1") (pintype "passive"))
    )
    (net (code "46") (name "Net-(U4-IN1_N)") (class "Default")
      (node (ref "C24") (pin "2") (pinfunction "2_2") (pintype "passive"))
      (node (ref "R50") (pin "1") (pinfunction "1_1") (pintype "passive"))
      (node (ref "U4") (pin "2") (pinfunction "IN1_N_2") (pintype "input"))
    )
    (net (code "47") (name "Net-(U4-IN1_P)") (class "Default")
      (node (ref "C47") (pin "1") (pinfunction "1_1") (pintype "passive"))
      (node (ref "R42") (pin "1") (pinfunction "1_1") (pintype "passive"))
      (node (ref "U4") (pin "3") (pinfunction "IN1_P_3") (pintype "input"))
    )
    (net (code "48") (name "Net-(U4-IN2_N)") (class "Default")
      (node (ref "C34") (pin "1") (pinfunction "1_1") (pintype "passive"))
      (node (ref "R56") (pin "1") (pinfunction "1_1") (pintype "passive"))
      (node (ref "U4") (pin "8") (pinfunction "IN2_N_8") (pintype "input"))
    )
    (net (code "49") (name "Net-(U4-IN2_P)") (class "Default")
      (node (ref "C48") (pin "2") (pinfunction "2_2") (pintype "passive"))
      (node (ref "R59") (pin "1") (pinfunction "1_1") (pintype "passive"))
      (node (ref "U4") (pin "7") (pinfunction "IN2_P_7") (pintype "input"))
    )
    (net (code "50") (name "Net-(U4-OUT1)") (class "Default")
      (node (ref "C24") (pin "1") (pinfunction "1_1") (pintype "passive"))
      (node (ref "R31") (pin "1") (pinfunction "1_1") (pintype "passive"))
      (node (ref "R32") (pin "1") (pinfunction "1_1") (pintype "passive"))
      (node (ref "R46") (pin "2") (pinfunction "2_2") (pintype "passive"))
      (node (ref "U4") (pin "1") (pinfunction "OUT1_1") (pintype "output"))
    )
    (net (code "51") (name "Net-(U4-OUT2)") (class "Default")
      (node (ref "C34") (pin "2") (pinfunction "2_2") (pintype "passive"))
      (node (ref "R52") (pin "2") (pinfunction "2_2") (pintype "passive"))
      (node (ref "R63") (pin "1") (pinfunction "1_1") (pintype "passive"))
      (node (ref "R71") (pin "1") (pinfunction "1_1") (pintype "passive"))
      (node (ref "U4") (pin "9") (pinfunction "OUT2_9") (pintype "output"))
    )
    (net (code "52") (name "Net-(U5-IN1_N)") (class "Default")
      (node (ref "C17") (pin "2") (pinfunction "2_2") (pintype "passive"))
      (node (ref "R109") (pin "2") (pinfunction "2_2") (pintype "passive"))
      (node (ref "R33") (pin "1") (pinfunction "1_1") (pintype "passive"))
      (node (ref "R36") (pin "2") (pinfunction "2_2") (pintype "passive"))
      (node (ref "U5") (pin "2") (pinfunction "IN1_N_2") (pintype "input"))
    )
    (net (code "53") (name "Net-(U5-IN1_P)") (class "Default")
      (node (ref "R114") (pin "2") (pinfunction "2_2") (pintype "passive"))
      (node (ref "R45") (pin "1") (pinfunction "1_1") (pintype "passive"))
      (node (ref "U5") (pin "3") (pinfunction "IN1_P_3") (pintype "input"))
    )
    (net (code "54") (name "Net-(U5-IN2_N)") (class "Default")
      (node (ref "C35") (pin "2") (pinfunction "2_2") (pintype "passive"))
      (node (ref "R110") (pin "1") (pinfunction "1_1") (pintype "passive"))
      (node (ref "R61") (pin "2") (pinfunction "2_2") (pintype "passive"))
      (node (ref "R65") (pin "1") (pinfunction "1_1") (pintype "passive"))
      (node (ref "U5") (pin "8") (pinfunction "IN2_N_8") (pintype "input"))
    )
    (net (code "55") (name "Net-(U5-IN2_P)") (class "Default")
      (node (ref "R115") (pin "1") (pinfunction "1_1") (pintype "passive"))
      (node (ref "R51") (pin "1") (pinfunction "1_1") (pintype "passive"))
      (node (ref "U5") (pin "7") (pinfunction "IN2_P_7") (pintype "input"))
    )
    (net (code "56") (name "Net-(U5-OUT1)") (class "Default")
      (node (ref "C17") (pin "1") (pinfunction "1_1") (pintype "passive"))
      (node (ref "R36") (pin "1") (pinfunction "1_1") (pintype "passive"))
      (node (ref "R48") (pin "2") (pinfunction "2_2") (pintype "passive"))
      (node (ref "U5") (pin "1") (pinfunction "OUT1_1") (pintype "output"))
    )
    (net (code "57") (name "Net-(U5-OUT2)") (class "Default")
      (node (ref "C35") (pin "1") (pinfunction "1_1") (pintype "passive"))
      (node (ref "R54") (pin "2") (pinfunction "2_2") (pintype "passive"))
      (node (ref "R61") (pin "1") (pinfunction "1_1") (pintype "passive"))
      (node (ref "U5") (pin "9") (pinfunction "OUT2_9") (pintype "output"))
    )
  )
)
